# main.net
KiCad netlist of a schematic drawn in EAGLE
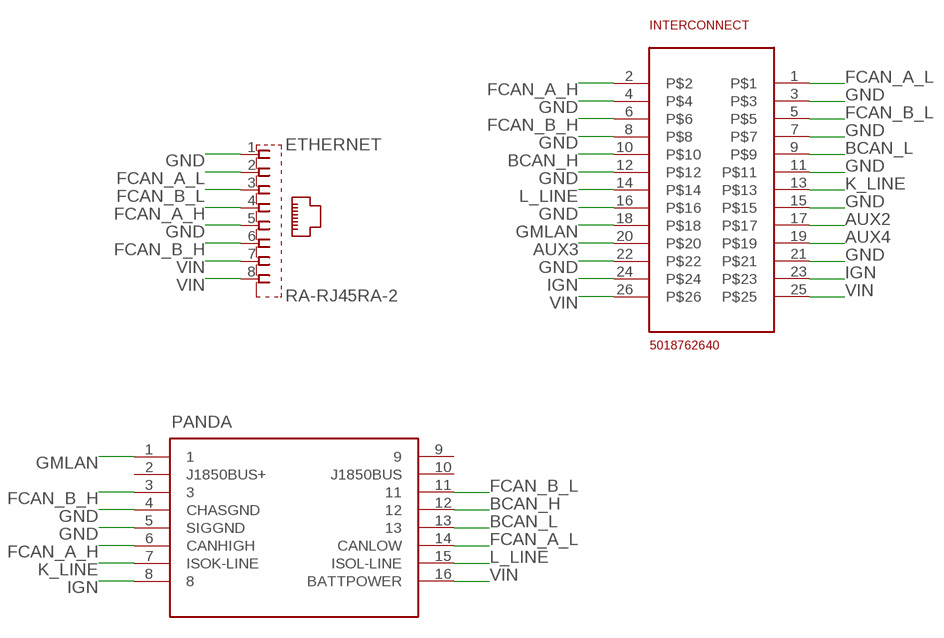
[diagram p0: schematic, sheet 1]

(export (version "E")
  (design (tool "Eeschema 10.0.6"))
  (components
    (comp (ref "ETHERNET")
      (value "RA-RJ45RA-2")
      (footprint "eagle-import:RA-RJ45-2")
      (libsource (lib "eagle-import") (part "RA-RJ45RA-2"))
    )
    (comp (ref "INTERCONNECT")
      (value "5018762640")
      (footprint "eagle-import:5018762640")
      (libsource (lib "eagle-import") (part "5018762640"))
    )
    (comp (ref "PANDA")
      (value "OBDII-FEMALEFEMALE")
      (footprint "eagle-import:OBDII-FEMALE")
      (libsource (lib "eagle-import") (part "OBDII-FEMALEFEMALE"))
    )
  )
  (nets
    (net (code "1") (name "/AUX2") (class "Default")
      (node (ref "INTERCONNECT") (pin "17") (pinfunction "P$17_17") (pintype "bidirectional"))
    )
    (net (code "2") (name "/AUX3") (class "Default")
      (node (ref "INTERCONNECT") (pin "20") (pinfunction "P$20_20") (pintype "bidirectional"))
    )
    (net (code "3") (name "/AUX4") (class "Default")
      (node (ref "INTERCONNECT") (pin "19") (pinfunction "P$19_19") (pintype "bidirectional"))
    )
    (net (code "4") (name "/BCAN_H") (class "Default")
      (node (ref "INTERCONNECT") (pin "10") (pinfunction "P$10_10") (pintype "bidirectional"))
      (node (ref "PANDA") (pin "12") (pinfunction "12_12") (pintype "bidirectional"))
    )
    (net (code "5") (name "/BCAN_L") (class "Default")
      (node (ref "INTERCONNECT") (pin "9") (pinfunction "P$9_9") (pintype "bidirectional"))
      (node (ref "PANDA") (pin "13") (pinfunction "13_13") (pintype "bidirectional"))
    )
    (net (code "6") (name "/FCAN_A_H") (class "Default")
      (node (ref "ETHERNET") (pin "4") (pinfunction "4_4") (pintype "passive"))
      (node (ref "INTERCONNECT") (pin "2") (pinfunction "P$2_2") (pintype "bidirectional"))
      (node (ref "PANDA") (pin "6") (pinfunction "CANHIGH_6") (pintype "bidirectional"))
    )
    (net (code "7") (name "/FCAN_A_L") (class "Default")
      (node (ref "ETHERNET") (pin "2") (pinfunction "2_2") (pintype "passive"))
      (node (ref "INTERCONNECT") (pin "1") (pinfunction "P$1_1") (pintype "bidirectional"))
      (node (ref "PANDA") (pin "14") (pinfunction "CANLOW_14") (pintype "bidirectional"))
    )
    (net (code "8") (name "/FCAN_B_H") (class "Default")
      (node (ref "ETHERNET") (pin "6") (pinfunction "6_6") (pintype "passive"))
      (node (ref "INTERCONNECT") (pin "6") (pinfunction "P$6_6") (pintype "bidirectional"))
      (node (ref "PANDA") (pin "3") (pinfunction "3_3") (pintype "bidirectional"))
    )
    (net (code "9") (name "/FCAN_B_L") (class "Default")
      (node (ref "ETHERNET") (pin "3") (pinfunction "3_3") (pintype "passive"))
      (node (ref "INTERCONNECT") (pin "5") (pinfunction "P$5_5") (pintype "bidirectional"))
      (node (ref "PANDA") (pin "11") (pinfunction "11_11") (pintype "bidirectional"))
    )
    (net (code "10") (name "/GMLAN") (class "Default")
      (node (ref "INTERCONNECT") (pin "18") (pinfunction "P$18_18") (pintype "bidirectional"))
      (node (ref "PANDA") (pin "1") (pinfunction "1_1") (pintype "bidirectional"))
    )
    (net (code "11") (name "/GND") (class "Default")
      (node (ref "ETHERNET") (pin "1") (pinfunction "1_1") (pintype "passive"))
      (node (ref "ETHERNET") (pin "5") (pinfunction "5_5") (pintype "passive"))
      (node (ref "INTERCONNECT") (pin "11") (pinfunction "P$11_11") (pintype "bidirectional"))
      (node (ref "INTERCONNECT") (pin "12") (pinfunction "P$12_12") (pintype "bidirectional"))
      (node (ref "INTERCONNECT") (pin "15") (pinfunction "P$15_15") (pintype "bidirectional"))
      (node (ref "INTERCONNECT") (pin "16") (pinfunction "P$16_16") (pintype "bidirectional"))
      (node (ref "INTERCONNECT") (pin "21") (pinfunction "P$21_21") (pintype "bidirectional"))
      (node (ref "INTERCONNECT") (pin "22") (pinfunction "P$22_22") (pintype "bidirectional"))
      (node (ref "INTERCONNECT") (pin "3") (pinfunction "P$3_3") (pintype "bidirectional"))
      (node (ref "INTERCONNECT") (pin "4") (pinfunction "P$4_4") (pintype "bidirectional"))
      (node (ref "INTERCONNECT") (pin "7") (pinfunction "P$7_7") (pintype "bidirectional"))
      (node (ref "INTERCONNECT") (pin "8") (pinfunction "P$8_8") (pintype "bidirectional"))
      (node (ref "PANDA") (pin "4") (pinfunction "CHASGND_4") (pintype "bidirectional"))
      (node (ref "PANDA") (pin "5") (pinfunction "SIGGND_5") (pintype "bidirectional"))
    )
    (net (code "12") (name "/IGN") (class "Default")
      (node (ref "INTERCONNECT") (pin "23") (pinfunction "P$23_23") (pintype "bidirectional"))
      (node (ref "INTERCONNECT") (pin "24") (pinfunction "P$24_24") (pintype "bidirectional"))
      (node (ref "PANDA") (pin "8") (pinfunction "8_8") (pintype "bidirectional"))
    )
    (net (code "13") (name "/K_LINE") (class "Default")
      (node (ref "INTERCONNECT") (pin "13") (pinfunction "P$13_13") (pintype "bidirectional"))
      (node (ref "PANDA") (pin "7") (pinfunction "ISOK-LINE_7") (pintype "bidirectional"))
    )
    (net (code "14") (name "/L_LINE") (class "Default")
      (node (ref "INTERCONNECT") (pin "14") (pinfunction "P$14_14") (pintype "bidirectional"))
      (node (ref "PANDA") (pin "15") (pinfunction "ISOL-LINE_15") (pintype "bidirectional"))
    )
    (net (code "15") (name "/VIN") (class "Default")
      (node (ref "ETHERNET") (pin "7") (pinfunction "7_7") (pintype "passive"))
      (node (ref "ETHERNET") (pin "8") (pinfunction "8_8") (pintype "passive"))
      (node (ref "INTERCONNECT") (pin "25") (pinfunction "P$25_25") (pintype "bidirectional"))
      (node (ref "INTERCONNECT") (pin "26") (pinfunction "P$26_26") (pintype "bidirectional"))
      (node (ref "PANDA") (pin "16") (pinfunction "BATTPOWER_16") (pintype "bidirectional"))
    )
    (net (code "16") (name "unconnected-(PANDA-J1850BUS+-Pad2)") (class "Default")
      (node (ref "PANDA") (pin "2") (pinfunction "J1850BUS+_2") (pintype "bidirectional"))
    )
    (net (code "17") (name "unconnected-(PANDA-J1850BUS-Pad10)") (class "Default")
      (node (ref "PANDA") (pin "10") (pinfunction "J1850BUS_10") (pintype "bidirectional"))
    )
    (net (code "18") (name "unconnected-(PANDA-Pad9)") (class "Default")
      (node (ref "PANDA") (pin "9") (pinfunction "9_9") (pintype "bidirectional"))
    )
  )
)
